# Source_Boat-Board.net
KiCad netlist of a schematic drawn in EasyEDA Pro
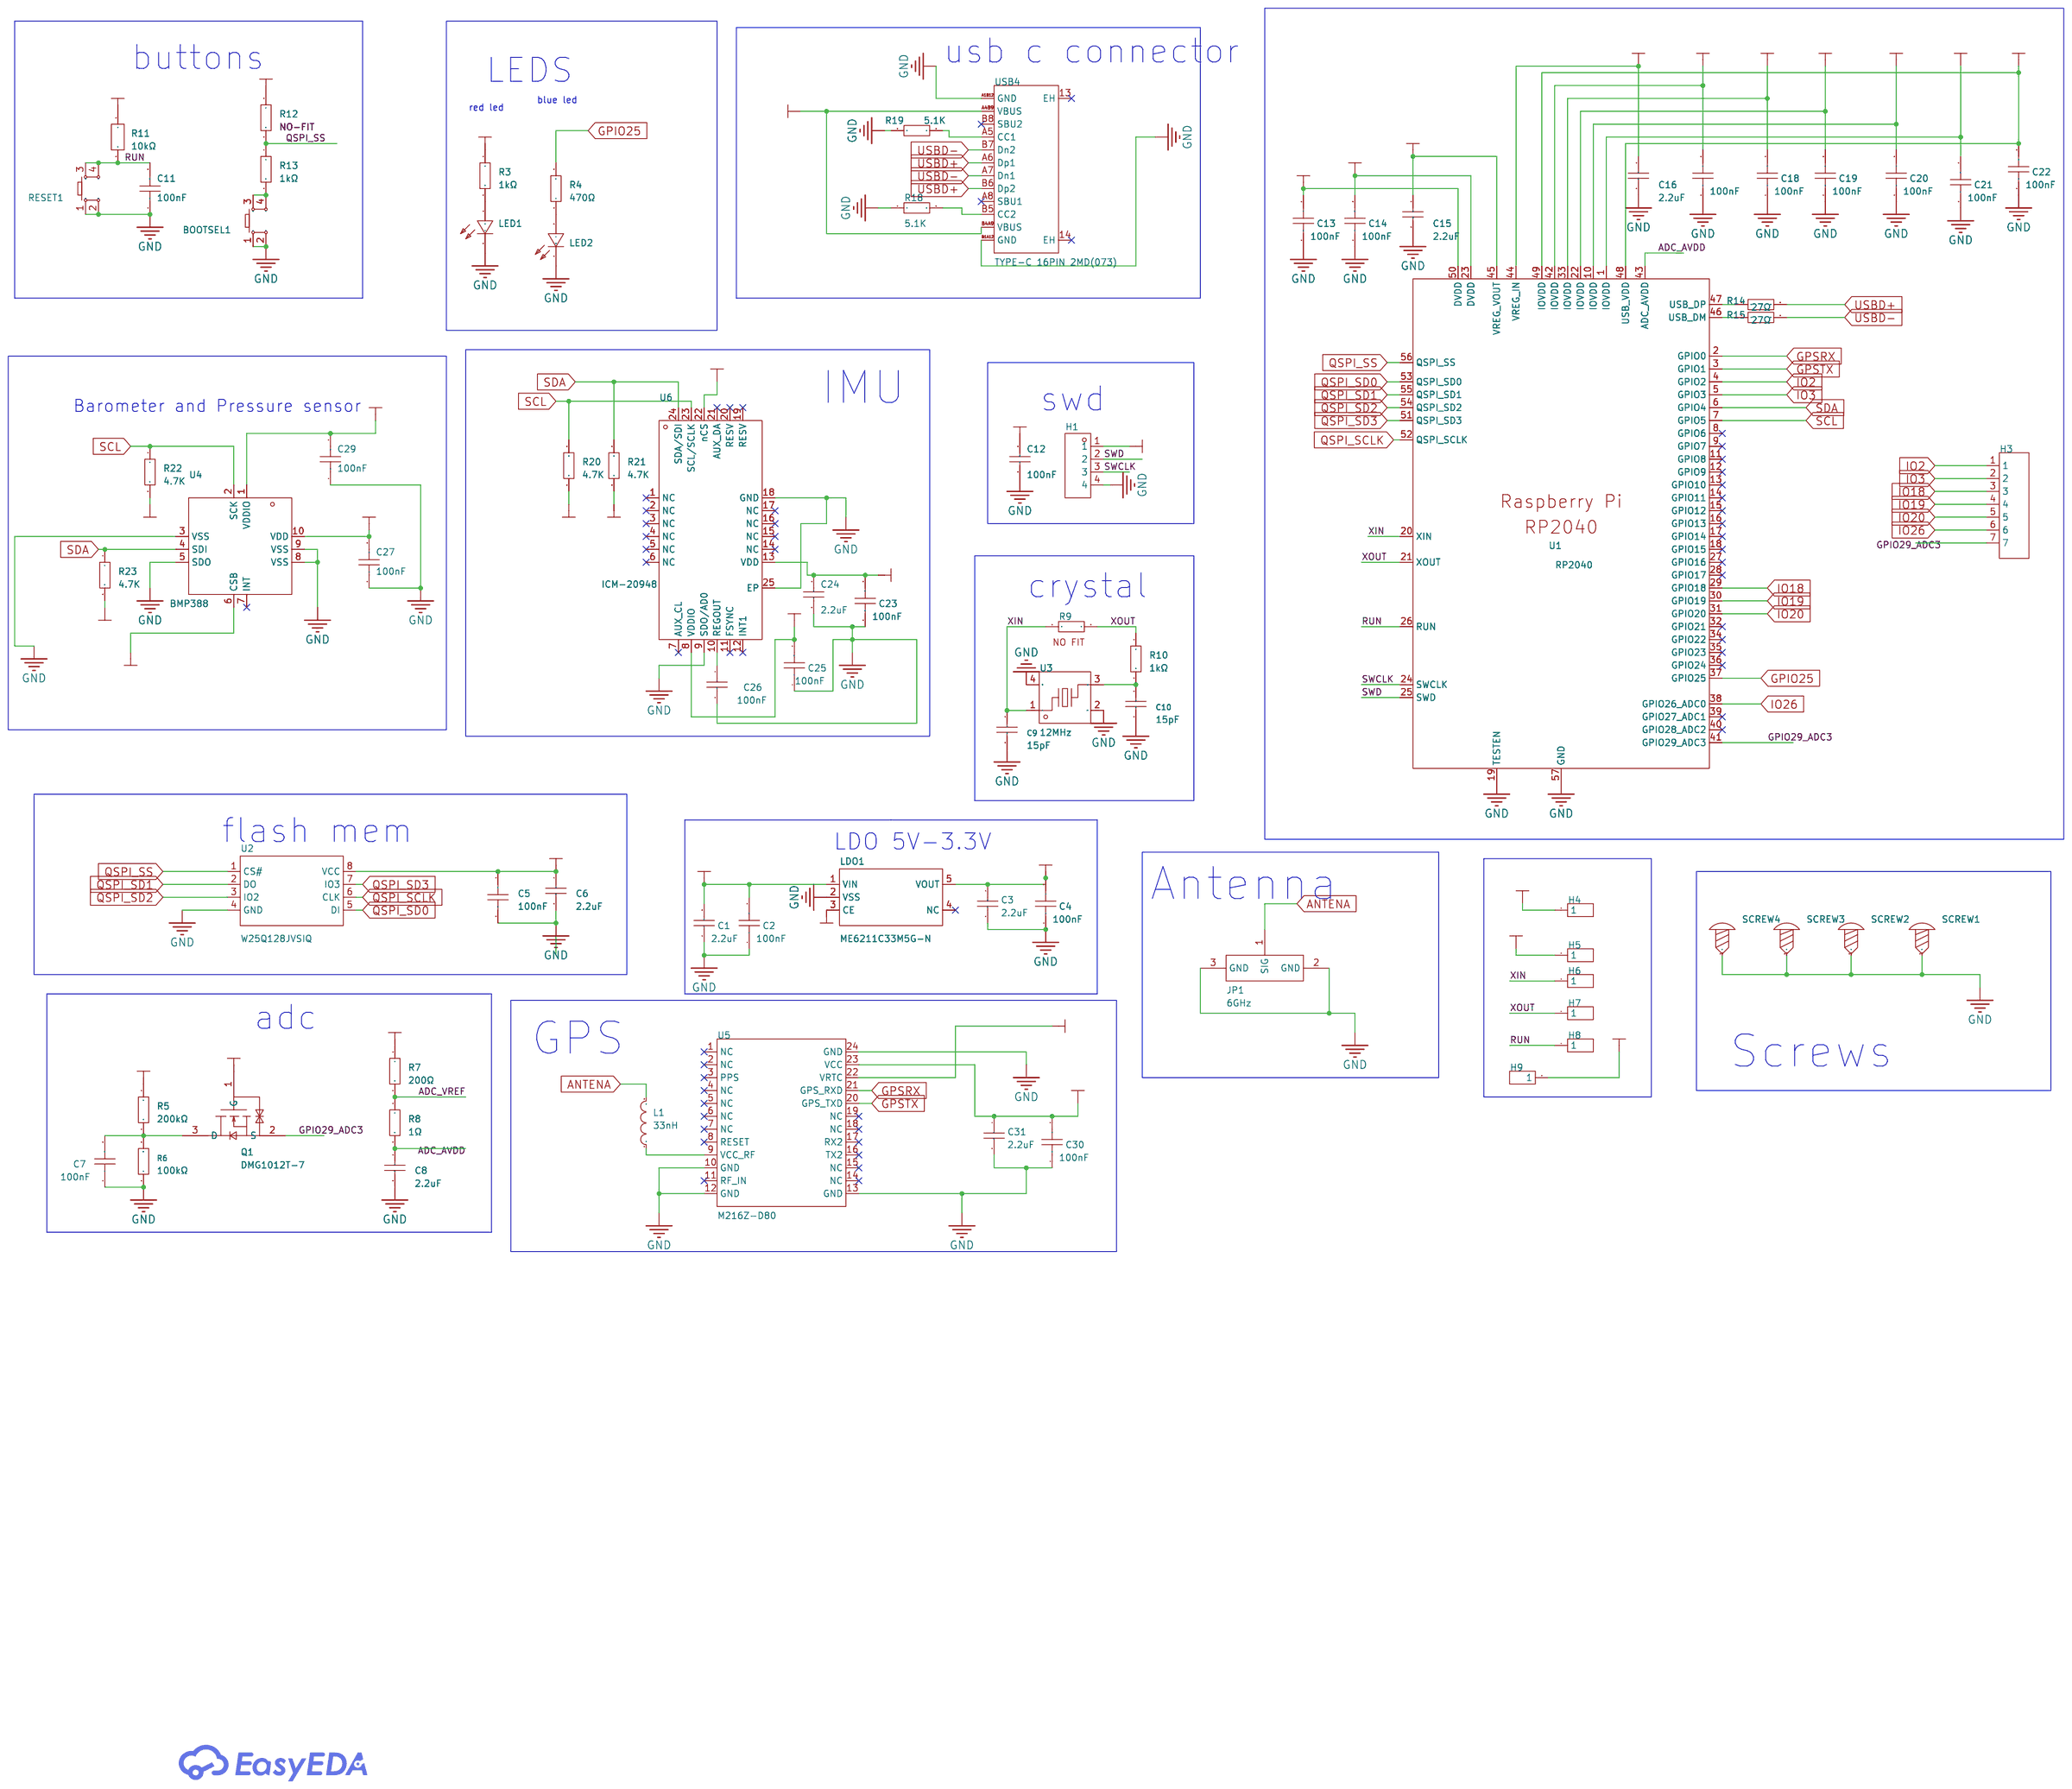
[diagram p0: schematic sheet]

(export (version "E")
  (design (tool "Eeschema 10.0.6"))
  (components
    (comp (ref "BOOTSEL1")
      (value "PTS815SJK250SMTRLFS")
      (footprint "easyedapro:SW-SMD_4P-L4.2-W3.3-P2.15-LS5.1")
      (description "操作寿命10万次，使用温度-20°C 至 70°C,尺寸4.20mmx3.20mmx2.50mm，操作力度2.5N")
      (fields (field (name "Manufacturer") "C&K"))
      (libsource (lib "easyedapro") (part "PTS815SJK250SMTRLFS"))
    )
    (comp (ref "C1")
      (value "2.2uF")
      (footprint "easyedapro:C0603")
      (description "Capacitance:2.2uF Tolerance:±10% Tolerance:±10% Voltage Rating:16V Temperature Coefficient:X5R")
      (fields
        (field (name "Manufacturer Part") "CL10A225KO8NNNC")
        (field (name "Manufacturer") "SAMSUNG(三星)")
      )
      (libsource (lib "easyedapro") (part "CL10A225KO8NNNC"))
    )
    (comp (ref "C2")
      (value "100nF")
      (footprint "easyedapro:C0603")
      (description "Capacitance:100nF Tolerance:±10% Tolerance:±10% Voltage Rating:50V Temperature Coefficient:X7R")
      (fields (field (name "Manufacturer Part") "0603B104K500AT") (field (name "Manufacturer") "FH(风华)"))
      (libsource (lib "easyedapro") (part "0603B104K500AT"))
    )
    (comp (ref "C3")
      (value "2.2uF")
      (footprint "easyedapro:C0603")
      (description "Capacitance:2.2uF Tolerance:±10% Tolerance:±10% Voltage Rating:16V Temperature Coefficient:X5R")
      (fields
        (field (name "Manufacturer Part") "CL10A225KO8NNNC")
        (field (name "Manufacturer") "SAMSUNG(三星)")
      )
      (libsource (lib "easyedapro") (part "CL10A225KO8NNNC"))
    )
    (comp (ref "C4")
      (value "100nF")
      (footprint "easyedapro:C0603")
      (description "Capacitance:100nF Tolerance:±10% Tolerance:±10% Voltage Rating:50V Temperature Coefficient:X7R")
      (fields (field (name "Manufacturer Part") "0603B104K500AT") (field (name "Manufacturer") "FH(风华)"))
      (libsource (lib "easyedapro") (part "0603B104K500AT"))
    )
    (comp (ref "C5")
      (value "100nF")
      (footprint "easyedapro:C0603")
      (description "Capacitance:100nF Tolerance:±10% Tolerance:±10% Voltage Rating:50V Temperature Coefficient:X7R")
      (fields
        (field (name "Manufacturer Part") "CC0603KRX7R9BB104")
        (field (name "Manufacturer") "YAGEO(国巨)")
      )
      (libsource (lib "easyedapro") (part "CC0603KRX7R9BB104"))
    )
    (comp (ref "C6")
      (value "2.2uF")
      (footprint "easyedapro:C0603")
      (description "Capacitance:2.2uF Tolerance:±10% Tolerance:±10% Voltage Rating:16V Temperature Coefficient:X5R")
      (fields
        (field (name "Manufacturer Part") "CL10A225KO8NNNC")
        (field (name "Manufacturer") "SAMSUNG(三星)")
      )
      (libsource (lib "easyedapro") (part "CL10A225KO8NNNC"))
    )
    (comp (ref "C7")
      (value "100nF")
      (footprint "easyedapro:C0603")
      (description "Capacitance:100nF Tolerance:±10% Tolerance:±10% Voltage Rating:50V Temperature Coefficient:X7R")
      (fields
        (field (name "Manufacturer Part") "CC0603KRX7R9BB104")
        (field (name "Manufacturer") "YAGEO(国巨)")
      )
      (libsource (lib "easyedapro") (part "CC0603KRX7R9BB104"))
    )
    (comp (ref "C8")
      (value "2.2uF")
      (footprint "easyedapro:C0603")
      (description "Capacitance:2.2uF Tolerance:±10% Tolerance:±10% Voltage Rating:16V Temperature Coefficient:X5R")
      (fields
        (field (name "Manufacturer Part") "CL10A225KO8NNNC")
        (field (name "Manufacturer") "SAMSUNG(三星)")
      )
      (libsource (lib "easyedapro") (part "CL10A225KO8NNNC"))
    )
    (comp (ref "C9")
      (value "15pF")
      (footprint "easyedapro:C0603")
      (description "Capacitance:15pF Tolerance:±5% Tolerance:±5% Voltage Rating:50V Temperature Coefficient:NP0")
      (fields
        (field (name "Manufacturer Part") "CC0603JRNPO9BN150")
        (field (name "Manufacturer") "YAGEO(国巨)")
      )
      (libsource (lib "easyedapro") (part "CC0603JRNPO9BN150"))
    )
    (comp (ref "C10")
      (value "15pF")
      (footprint "easyedapro:C0603")
      (description "Capacitance:15pF Tolerance:±5% Tolerance:±5% Voltage Rating:50V Temperature Coefficient:NP0")
      (fields
        (field (name "Manufacturer Part") "CC0603JRNPO9BN150")
        (field (name "Manufacturer") "YAGEO(国巨)")
      )
      (libsource (lib "easyedapro") (part "CC0603JRNPO9BN150"))
    )
    (comp (ref "C11")
      (value "100nF")
      (footprint "easyedapro:C0603")
      (description "Capacitance:100nF Tolerance:±10% Tolerance:±10% Voltage Rating:50V Temperature Coefficient:X7R")
      (fields (field (name "Manufacturer Part") "0603B104K500AT") (field (name "Manufacturer") "FH(风华)"))
      (libsource (lib "easyedapro") (part "0603B104K500AT"))
    )
    (comp (ref "C12")
      (value "100nF")
      (footprint "easyedapro:C0603")
      (description "Capacitance:100nF Tolerance:±10% Tolerance:±10% Voltage Rating:50V Temperature Coefficient:X7R")
      (fields (field (name "Manufacturer Part") "0603B104K500NT") (field (name "Manufacturer") "FH(风华)"))
      (libsource (lib "easyedapro") (part "0603B104K500NT"))
    )
    (comp (ref "C13")
      (value "100nF")
      (footprint "easyedapro:C0603")
      (description "Capacitance:100nF Tolerance:±10% Tolerance:±10% Voltage Rating:50V Temperature Coefficient:X7R")
      (fields (field (name "Manufacturer Part") "0603B104K500AT") (field (name "Manufacturer") "FH(风华)"))
      (libsource (lib "easyedapro") (part "0603B104K500AT"))
    )
    (comp (ref "C14")
      (value "100nF")
      (footprint "easyedapro:C0603")
      (description "Capacitance:100nF Tolerance:±10% Tolerance:±10% Voltage Rating:50V Temperature Coefficient:X7R")
      (fields (field (name "Manufacturer Part") "0603B104K500AT") (field (name "Manufacturer") "FH(风华)"))
      (libsource (lib "easyedapro") (part "0603B104K500AT"))
    )
    (comp (ref "C15")
      (value "2.2uF")
      (footprint "easyedapro:C0603")
      (description "Capacitance:2.2uF Tolerance:±10% Tolerance:±10% Voltage Rating:16V Temperature Coefficient:X5R")
      (fields
        (field (name "Manufacturer Part") "CL10A225KO8NNNC")
        (field (name "Manufacturer") "SAMSUNG(三星)")
      )
      (libsource (lib "easyedapro") (part "CL10A225KO8NNNC"))
    )
    (comp (ref "C16")
      (value "2.2uF")
      (footprint "easyedapro:C0603")
      (description "Capacitance:2.2uF Tolerance:±10% Tolerance:±10% Voltage Rating:16V Temperature Coefficient:X5R")
      (fields
        (field (name "Manufacturer Part") "CL10A225KO8NNNC")
        (field (name "Manufacturer") "SAMSUNG(三星)")
      )
      (libsource (lib "easyedapro") (part "CL10A225KO8NNNC"))
    )
    (comp (ref "C17")
      (value "100nF")
      (footprint "easyedapro:C0603")
      (description "Capacitance:100nF Tolerance:±10% Tolerance:±10% Voltage Rating:50V Temperature Coefficient:X7R")
      (fields (field (name "Manufacturer Part") "0603B104K500AT") (field (name "Manufacturer") "FH(风华)"))
      (libsource (lib "easyedapro") (part "0603B104K500AT"))
    )
    (comp (ref "C18")
      (value "100nF")
      (footprint "easyedapro:C0603")
      (description "Capacitance:100nF Tolerance:±10% Tolerance:±10% Voltage Rating:50V Temperature Coefficient:X7R")
      (fields (field (name "Manufacturer Part") "0603B104K500AT") (field (name "Manufacturer") "FH(风华)"))
      (libsource (lib "easyedapro") (part "0603B104K500AT"))
    )
    (comp (ref "C19")
      (value "100nF")
      (footprint "easyedapro:C0603")
      (description "Capacitance:100nF Tolerance:±10% Tolerance:±10% Voltage Rating:50V Temperature Coefficient:X7R")
      (fields (field (name "Manufacturer Part") "0603B104K500AT") (field (name "Manufacturer") "FH(风华)"))
      (libsource (lib "easyedapro") (part "0603B104K500AT"))
    )
    (comp (ref "C20")
      (value "100nF")
      (footprint "easyedapro:C0603")
      (description "Capacitance:100nF Tolerance:±10% Tolerance:±10% Voltage Rating:50V Temperature Coefficient:X7R")
      (fields (field (name "Manufacturer Part") "0603B104K500AT") (field (name "Manufacturer") "FH(风华)"))
      (libsource (lib "easyedapro") (part "0603B104K500AT"))
    )
    (comp (ref "C21")
      (value "100nF")
      (footprint "easyedapro:C0603")
      (description "Capacitance:100nF Tolerance:±10% Tolerance:±10% Voltage Rating:50V Temperature Coefficient:X7R")
      (fields (field (name "Manufacturer Part") "0603B104K500AT") (field (name "Manufacturer") "FH(风华)"))
      (libsource (lib "easyedapro") (part "0603B104K500AT"))
    )
    (comp (ref "C22")
      (value "100nF")
      (footprint "easyedapro:C0603")
      (description "Capacitance:100nF Tolerance:±10% Tolerance:±10% Voltage Rating:50V Temperature Coefficient:X7R")
      (fields (field (name "Manufacturer Part") "0603B104K500AT") (field (name "Manufacturer") "FH(风华)"))
      (libsource (lib "easyedapro") (part "0603B104K500AT"))
    )
    (comp (ref "C23")
      (value "100nF")
      (footprint "easyedapro:C0603")
      (description "Capacitance:100nF Tolerance:±10% Tolerance:±10% Voltage Rating:50V Temperature Coefficient:X7R")
      (fields (field (name "Manufacturer Part") "0603B104K500AT") (field (name "Manufacturer") "FH(风华)"))
      (libsource (lib "easyedapro") (part "0603B104K500AT"))
    )
    (comp (ref "C24")
      (value "2.2uF")
      (footprint "easyedapro:C0603")
      (description "Capacitance:2.2uF Tolerance:±10% Tolerance:±10% Voltage Rating:16V Temperature Coefficient:X5R")
      (fields
        (field (name "Manufacturer Part") "CL10A225KO8NNNC")
        (field (name "Manufacturer") "SAMSUNG(三星)")
      )
      (libsource (lib "easyedapro") (part "CL10A225KO8NNNC"))
    )
    (comp (ref "C25")
      (value "100nF")
      (footprint "easyedapro:C0603")
      (description "Capacitance:100nF Tolerance:±10% Tolerance:±10% Voltage Rating:50V Temperature Coefficient:X7R")
      (fields (field (name "Manufacturer Part") "0603B104K500AT") (field (name "Manufacturer") "FH(风华)"))
      (libsource (lib "easyedapro") (part "0603B104K500AT"))
    )
    (comp (ref "C26")
      (value "100nF")
      (footprint "easyedapro:C0603")
      (description "Capacitance:100nF Tolerance:±10% Tolerance:±10% Voltage Rating:50V Temperature Coefficient:X7R")
      (fields (field (name "Manufacturer Part") "0603B104K500NT") (field (name "Manufacturer") "FH(风华)"))
      (libsource (lib "easyedapro") (part "0603B104K500NT"))
    )
    (comp (ref "C27")
      (value "100nF")
      (footprint "easyedapro:C0603")
      (description "Capacitance:100nF Tolerance:±10% Tolerance:±10% Voltage Rating:50V Temperature Coefficient:X7R")
      (fields (field (name "Manufacturer Part") "0603B104K500AT") (field (name "Manufacturer") "FH(风华)"))
      (libsource (lib "easyedapro") (part "0603B104K500AT"))
    )
    (comp (ref "C29")
      (value "100nF")
      (footprint "easyedapro:C0603")
      (description "Capacitance:100nF Tolerance:±10% Tolerance:±10% Voltage Rating:50V Temperature Coefficient:X7R")
      (fields (field (name "Manufacturer Part") "0603B104K500AT") (field (name "Manufacturer") "FH(风华)"))
      (libsource (lib "easyedapro") (part "0603B104K500AT"))
    )
    (comp (ref "C30")
      (value "100nF")
      (footprint "easyedapro:C0603")
      (description "Capacitance:100nF Tolerance:±10% Tolerance:±10% Voltage Rating:50V Temperature Coefficient:X7R")
      (fields (field (name "Manufacturer Part") "0603B104K500AT") (field (name "Manufacturer") "FH(风华)"))
      (libsource (lib "easyedapro") (part "0603B104K500AT"))
    )
    (comp (ref "C31")
      (value "2.2uF")
      (footprint "easyedapro:C0603")
      (description "Capacitance:2.2uF Tolerance:±10% Tolerance:±10% Voltage Rating:16V Temperature Coefficient:X5R")
      (fields
        (field (name "Manufacturer Part") "CL10A225KO8NNNC")
        (field (name "Manufacturer") "SAMSUNG(三星)")
      )
      (libsource (lib "easyedapro") (part "CL10A225KO8NNNC"))
    )
    (comp (ref "H1")
      (value "DZ254W-11-04-65")
      (footprint "easyedapro:HDR-TH_4P-P2.54-H-M-W10.3")
      (fields (field (name "Manufacturer") "DEALON(德艺隆)"))
      (libsource (lib "easyedapro") (part "DZ254W-11-04-65"))
    )
    (comp (ref "H3")
      (value "~")
      (footprint "easyedapro:HDR-TH_7P-P2.54-V-F")
      (libsource (lib "easyedapro") (part "220S-1*7P H=8.5MM Ytype Gold-plated"))
    )
    (comp (ref "H4")
      (value "~")
      (footprint "easyedapro:HDR-TH_1P-V-M_XKB_X4611WV-01I-C28D40")
      (libsource (lib "easyedapro") (part "HDR_1x1"))
    )
    (comp (ref "H5")
      (value "~")
      (footprint "easyedapro:HDR-TH_1P-V-M_XKB_X4611WV-01I-C28D40")
      (libsource (lib "easyedapro") (part "HDR_1x1"))
    )
    (comp (ref "H6")
      (value "~")
      (footprint "easyedapro:HDR-TH_1P-V-M_XKB_X4611WV-01I-C28D40")
      (libsource (lib "easyedapro") (part "HDR_1x1"))
    )
    (comp (ref "H7")
      (value "~")
      (footprint "easyedapro:HDR-TH_1P-V-M_XKB_X4611WV-01I-C28D40")
      (libsource (lib "easyedapro") (part "HDR_1x1"))
    )
    (comp (ref "H8")
      (value "~")
      (footprint "easyedapro:HDR-TH_1P-V-M_XKB_X4611WV-01I-C28D40")
      (libsource (lib "easyedapro") (part "HDR_1x1"))
    )
    (comp (ref "H9")
      (value "~")
      (footprint "easyedapro:HDR-TH_1P-V-M_XKB_X4611WV-01I-C28D40")
      (libsource (lib "easyedapro") (part "HDR_1x1"))
    )
    (comp (ref "JP1")
      (value "6GHz")
      (footprint "easyedapro:RF-SMD_FRF05002-JSS103M")
      (fields (field (name "Manufacturer Part") "U.FL-R-SMT-1(80)") (field (name "Manufacturer") "HRS(广濑)"))
      (libsource (lib "easyedapro") (part "U.FL-R-SMT-1(80)"))
    )
    (comp (ref "L1") (value "33nH") (footprint "easyedapro:L0603") (libsource (lib "easyedapro") (part "电感")))
    (comp (ref "LDO1")
      (value "ME6211C33M5G-N")
      (footprint "easyedapro:SOT-23-5_L3.0-W1.7-P0.95-LS2.8-BL")
      (fields (field (name "Manufacturer") "MICRONE(南京微盟)"))
      (libsource (lib "easyedapro") (part "ME6211C33M5G-N"))
    )
    (comp (ref "LED1")
      (value "NCD0603R1")
      (footprint "easyedapro:LED0603-RD_RED")
      (fields (field (name "Manufacturer") "国星光电"))
      (libsource (lib "easyedapro") (part "FC-DA1608HRK-620D"))
    )
    (comp (ref "LED2")
      (value "19-217/BHC-ZL1M2RY/3T")
      (footprint "easyedapro:LED0603-FD_BLUE")
      (fields (field (name "Manufacturer") "EVERLIGHT(亿光)"))
      (libsource (lib "easyedapro") (part "19-217/BHC-ZL1M2RY/3T"))
    )
    (comp (ref "Q1")
      (value "DMG1012T-7")
      (footprint "easyedapro:SOT-523-3_L1.6-W0.8-P1.00-LS1.6-BR")
      (fields (field (name "Manufacturer") "DIODES(美台)"))
      (libsource (lib "easyedapro") (part "DMG1012T-7"))
    )
    (comp (ref "R3")
      (value "1kΩ")
      (footprint "easyedapro:R0603")
      (fields (field (name "Manufacturer Part") "RC0603FR-071KL") (field (name "Manufacturer") "YAGEO(国巨)"))
      (libsource (lib "easyedapro") (part "RC0603FR-071KL"))
    )
    (comp (ref "R4")
      (value "470Ω")
      (footprint "easyedapro:R0603")
      (fields (field (name "Manufacturer Part") "RC0603FR-07470RL") (field (name "Manufacturer") "YAGEO(国巨)"))
      (libsource (lib "easyedapro") (part "RC0603FR-07470RL"))
    )
    (comp (ref "R5")
      (value "200kΩ")
      (footprint "easyedapro:R0603")
      (fields (field (name "Manufacturer Part") "RC0603FR-07200KL") (field (name "Manufacturer") "YAGEO(国巨)"))
      (libsource (lib "easyedapro") (part "RC0603FR-07200KL"))
    )
    (comp (ref "R6")
      (value "100kΩ")
      (footprint "easyedapro:R0603")
      (fields (field (name "Manufacturer Part") "RC0603FR-07100KL") (field (name "Manufacturer") "YAGEO(国巨)"))
      (libsource (lib "easyedapro") (part "RC0603FR-07100KL"))
    )
    (comp (ref "R7")
      (value "200Ω")
      (footprint "easyedapro:R0603")
      (fields (field (name "Manufacturer Part") "RC0603FR-07200RL") (field (name "Manufacturer") "YAGEO(国巨)"))
      (libsource (lib "easyedapro") (part "RC0603FR-07200RL"))
    )
    (comp (ref "R8")
      (value "1Ω")
      (footprint "easyedapro:R0603")
      (fields (field (name "Manufacturer Part") "RC0603FR-071RL") (field (name "Manufacturer") "YAGEO(国巨)"))
      (libsource (lib "easyedapro") (part "RC0603FR-071RL"))
    )
    (comp (ref "R9")
      (value "NO FIT")
      (footprint "easyedapro:R0603")
      (libsource (lib "easyedapro") (part "Res"))
    )
    (comp (ref "R10")
      (value "1kΩ")
      (footprint "easyedapro:R0603")
      (fields (field (name "Manufacturer Part") "RC0603FR-071KL") (field (name "Manufacturer") "YAGEO(国巨)"))
      (libsource (lib "easyedapro") (part "RC0603FR-071KL"))
    )
    (comp (ref "R11")
      (value "10kΩ")
      (footprint "easyedapro:R0603")
      (fields
        (field (name "Manufacturer Part") "NQ03WAF1002T5E")
        (field (name "Manufacturer") "UNI-ROYAL(厚声)")
      )
      (libsource (lib "easyedapro") (part "NQ03WAF1002T5E"))
    )
    (comp (ref "R12")
      (value "NO-FIT")
      (footprint "easyedapro:R0603")
      (libsource (lib "easyedapro") (part "Res"))
    )
    (comp (ref "R13")
      (value "1kΩ")
      (footprint "easyedapro:R0603")
      (fields (field (name "Manufacturer Part") "RC0603FR-071KL") (field (name "Manufacturer") "YAGEO(国巨)"))
      (libsource (lib "easyedapro") (part "RC0603FR-071KL"))
    )
    (comp (ref "R14")
      (value "27Ω")
      (footprint "easyedapro:R0603")
      (description "电阻类型:厚膜电阻;阻值:27Ω;精度:±1%;功率:100mW;温度系数:±200ppm/°C;最大工作电压:75V;工作温度范围:-55°C~+155°C;")
      (fields
        (field (name "Manufacturer Part") "0603WAF270JT5E")
        (field (name "Manufacturer") "UNI-ROYAL(厚声)")
      )
      (libsource (lib "easyedapro") (part "0603WAF270JT5E"))
    )
    (comp (ref "R15")
      (value "27Ω")
      (footprint "easyedapro:R0603")
      (description "电阻类型:厚膜电阻;阻值:27Ω;精度:±1%;功率:100mW;温度系数:±200ppm/°C;最大工作电压:75V;工作温度范围:-55°C~+155°C;")
      (fields
        (field (name "Manufacturer Part") "0603WAF270JT5E")
        (field (name "Manufacturer") "UNI-ROYAL(厚声)")
      )
      (libsource (lib "easyedapro") (part "0603WAF270JT5E"))
    )
    (comp (ref "R18")
      (value "5.1K")
      (footprint "easyedapro:R0603")
      (libsource (lib "easyedapro") (part "Res"))
    )
    (comp (ref "R19")
      (value "5.1K")
      (footprint "easyedapro:R0603")
      (libsource (lib "easyedapro") (part "Res"))
    )
    (comp (ref "R20")
      (value "4.7K")
      (footprint "easyedapro:R0603")
      (libsource (lib "easyedapro") (part "Res"))
    )
    (comp (ref "R21")
      (value "4.7K")
      (footprint "easyedapro:R0603")
      (libsource (lib "easyedapro") (part "Res"))
    )
    (comp (ref "R22")
      (value "4.7K")
      (footprint "easyedapro:R0603")
      (libsource (lib "easyedapro") (part "Res"))
    )
    (comp (ref "R23")
      (value "4.7K")
      (footprint "easyedapro:R0603")
      (libsource (lib "easyedapro") (part "Res"))
    )
    (comp (ref "RESET1")
      (value "PTS815SJK250SMTRLFS")
      (footprint "easyedapro:SW-SMD_4P-L4.2-W3.3-P2.15-LS5.1")
      (description "操作寿命10万次，使用温度-20°C 至 70°C,尺寸4.20mmx3.20mmx2.50mm，操作力度2.5N")
      (fields (field (name "Manufacturer") "C&K"))
      (libsource (lib "easyedapro") (part "PTS815SJK250SMTRLFS"))
    )
    (comp (ref "SCREW1")
      (value "~")
      (footprint "easyedapro:Screw-Hole-M2")
      (libsource (lib "easyedapro") (part "Screw-Hole"))
    )
    (comp (ref "SCREW2")
      (value "~")
      (footprint "easyedapro:Screw-Hole-M2")
      (libsource (lib "easyedapro") (part "Screw-Hole"))
    )
    (comp (ref "SCREW3")
      (value "~")
      (footprint "easyedapro:Screw-Hole-M2")
      (libsource (lib "easyedapro") (part "Screw-Hole"))
    )
    (comp (ref "SCREW4")
      (value "~")
      (footprint "easyedapro:Screw-Hole-M2")
      (libsource (lib "easyedapro") (part "Screw-Hole"))
    )
    (comp (ref "U1")
      (value "RP2040")
      (footprint "easyedapro:LQFN-56_L7.0-W7.0-P0.4-EP")
      (description "CPU Core:- CPU Maximum Speed:133MHz Number of I/O:30 ADC (Bit):12bit")
      (fields (field (name "Manufacturer") "Raspberry Pi(树莓派)"))
      (libsource (lib "easyedapro") (part "RP2040"))
    )
    (comp (ref "U2")
      (value "W25Q128JVSIQ")
      (footprint "easyedapro:SOIC-8_L5.3-W5.3-P1.27-LS8.0-BL")
      (fields (field (name "Manufacturer") "Winbond(华邦)"))
      (libsource (lib "easyedapro") (part "W25Q128JVSIQTR"))
    )
    (comp (ref "U3")
      (value "12MHz")
      (footprint "easyedapro:CRYSTAL-SMD_4P-L3.2-W2.5-BL")
      (fields
        (field (name "Manufacturer Part") "0132M412000F10FTNNL")
        (field (name "Manufacturer") "HCI(杭晶)")
      )
      (libsource (lib "easyedapro") (part "0132M412000F10FTNNL"))
    )
    (comp (ref "U4")
      (value "BMP388")
      (footprint "easyedapro:SENSORM-SMD_BMP388")
      (fields (field (name "Manufacturer") "Bosch(博世)"))
      (libsource (lib "easyedapro") (part "BMP388"))
    )
    (comp (ref "U5")
      (value "M216Z-D80")
      (footprint "easyedapro:LCC-24_L16.3-W12.2_NEO-NEO-M10")
      (fields (field (name "Manufacturer") "如般微"))
      (libsource (lib "easyedapro") (part "M216Z-D80"))
    )
    (comp (ref "U6")
      (value "ICM-20948")
      (footprint "easyedapro:QFN-24_L3.0-W3.0-P0.40-BL-EP")
      (fields (field (name "Manufacturer") "TDK InvenSense(应美盛)"))
      (libsource (lib "easyedapro") (part "ICM-20948"))
    )
    (comp (ref "USB4")
      (value "TYPE-C 16PIN 2MD(073)")
      (footprint "easyedapro:USB-C-SMD_TYPE-C-16PIN-2MD-073")
      (fields (field (name "Manufacturer") "SHOU HAN(首韩)"))
      (libsource (lib "easyedapro") (part "TYPE-C 16PIN 2MD(073)"))
    )
  )
  (nets
    (net (code "1") (name "/ADC_AVDD") (class "Default")
      (node (ref "C8") (pin "1") (pinfunction "1_1") (pintype "input"))
      (node (ref "R8") (pin "2") (pinfunction "2_2") (pintype "input"))
      (node (ref "U1") (pin "43") (pinfunction "ADC_AVDD_43") (pintype "bidirectional"))
    )
    (net (code "2") (name "/ADC_VREF") (class "Default")
      (node (ref "R7") (pin "2") (pinfunction "2_2") (pintype "input"))
      (node (ref "R8") (pin "1") (pinfunction "1_1") (pintype "input"))
    )
    (net (code "3") (name "/GPIO29_ADC3") (class "Default")
      (node (ref "H3") (pin "7") (pinfunction "7_7") (pintype "unspecified"))
      (node (ref "Q1") (pin "2") (pinfunction "S_2") (pintype "unspecified"))
      (node (ref "U1") (pin "41") (pinfunction "GPIO29_ADC3_41") (pintype "bidirectional"))
    )
    (net (code "4") (name "/RUN") (class "Default")
      (node (ref "C11") (pin "2") (pinfunction "2_2") (pintype "unspecified"))
      (node (ref "H8") (pin "1") (pinfunction "1_1") (pintype "unspecified"))
      (node (ref "R11") (pin "2") (pinfunction "2_2") (pintype "unspecified"))
      (node (ref "RESET1") (pin "3") (pinfunction "3_3") (pintype "input"))
      (node (ref "RESET1") (pin "4") (pinfunction "4_4") (pintype "input"))
      (node (ref "U1") (pin "26") (pinfunction "RUN_26") (pintype "input"))
    )
    (net (code "5") (name "/SWCLK") (class "Default")
      (node (ref "H1") (pin "3") (pinfunction "3_3") (pintype "input"))
      (node (ref "U1") (pin "24") (pinfunction "SWCLK_24") (pintype "output"))
    )
    (net (code "6") (name "/SWD") (class "Default")
      (node (ref "H1") (pin "2") (pinfunction "2_2") (pintype "input"))
      (node (ref "U1") (pin "25") (pinfunction "SWD_25") (pintype "bidirectional"))
    )
    (net (code "7") (name "/XIN") (class "Default")
      (node (ref "C9") (pin "2") (pinfunction "2_2") (pintype "input"))
      (node (ref "H6") (pin "1") (pinfunction "1_1") (pintype "unspecified"))
      (node (ref "R9") (pin "1") (pinfunction "1_1") (pintype "input"))
      (node (ref "U1") (pin "20") (pinfunction "XIN_20") (pintype "input"))
      (node (ref "U3") (pin "1") (pinfunction "1_1") (pintype "input"))
    )
    (net (code "8") (name "/XOUT") (class "Default")
      (node (ref "H7") (pin "1") (pinfunction "1_1") (pintype "unspecified"))
      (node (ref "R10") (pin "1") (pinfunction "1_1") (pintype "input"))
      (node (ref "R9") (pin "2") (pinfunction "2_2") (pintype "input"))
      (node (ref "U1") (pin "21") (pinfunction "XOUT_21") (pintype "unspecified"))
    )
    (net (code "9") (name "1V1") (class "Default")
      (node (ref "C13") (pin "2") (pinfunction "2_2") (pintype "unspecified"))
      (node (ref "C14") (pin "2") (pinfunction "2_2") (pintype "unspecified"))
      (node (ref "C15") (pin "1") (pinfunction "1_1") (pintype "input"))
      (node (ref "H5") (pin "1") (pinfunction "1_1") (pintype "unspecified"))
      (node (ref "U1") (pin "23") (pinfunction "DVDD_23") (pintype "bidirectional"))
      (node (ref "U1") (pin "45") (pinfunction "VREG_VOUT_45") (pintype "bidirectional"))
      (node (ref "U1") (pin "50") (pinfunction "DVDD_50") (pintype "bidirectional"))
    )
    (net (code "10") (name "3V3") (class "Default")
      (node (ref "C12") (pin "1") (pinfunction "1_1") (pintype "input"))
      (node (ref "C16") (pin "1") (pinfunction "1_1") (pintype "input"))
      (node (ref "C17") (pin "2") (pinfunction "2_2") (pintype "unspecified"))
      (node (ref "C18") (pin "2") (pinfunction "2_2") (pintype "unspecified"))
      (node (ref "C19") (pin "2") (pinfunction "2_2") (pintype "unspecified"))
      (node (ref "C20") (pin "2") (pinfunction "2_2") (pintype "unspecified"))
      (node (ref "C21") (pin "2") (pinfunction "2_2") (pintype "unspecified"))
      (node (ref "C22") (pin "2") (pinfunction "2_2") (pintype "unspecified"))
      (node (ref "C23") (pin "2") (pinfunction "2_2") (pintype "unspecified"))
      (node (ref "C24") (pin "1") (pinfunction "1_1") (pintype "input"))
      (node (ref "C25") (pin "2") (pinfunction "2_2") (pintype "unspecified"))
      (node (ref "C27") (pin "2") (pinfunction "2_2") (pintype "unspecified"))
      (node (ref "C29") (pin "2") (pinfunction "2_2") (pintype "unspecified"))
      (node (ref "C3") (pin "1") (pinfunction "1_1") (pintype "input"))
      (node (ref "C30") (pin "2") (pinfunction "2_2") (pintype "unspecified"))
      (node (ref "C31") (pin "1") (pinfunction "1_1") (pintype "input"))
      (node (ref "C4") (pin "2") (pinfunction "2_2") (pintype "unspecified"))
      (node (ref "C5") (pin "1") (pinfunction "1_1") (pintype "unspecified"))
      (node (ref "C6") (pin "1") (pinfunction "1_1") (pintype "input"))
      (node (ref "H1") (pin "1") (pinfunction "1_1") (pintype "input"))
      (node (ref "H4") (pin "1") (pinfunction "1_1") (pintype "unspecified"))
      (node (ref "LDO1") (pin "5") (pinfunction "VOUT_5") (pintype "unspecified"))
      (node (ref "Q1") (pin "1") (pinfunction "G_1") (pintype "unspecified"))
      (node (ref "R11") (pin "1") (pinfunction "1_1") (pintype "unspecified"))
      (node (ref "R12") (pin "1") (pinfunction "1_1") (pintype "input"))
      (node (ref "R20") (pin "2") (pinfunction "2_2") (pintype "input"))
      (node (ref "R21") (pin "2") (pinfunction "2_2") (pintype "input"))
      (node (ref "R22") (pin "2") (pinfunction "2_2") (pintype "input"))
      (node (ref "R23") (pin "2") (pinfunction "2_2") (pintype "input"))
      (node (ref "R3") (pin "1") (pinfunction "1_1") (pintype "input"))
      (node (ref "R7") (pin "1") (pinfunction "1_1") (pintype "input"))
      (node (ref "U1") (pin "1") (pinfunction "IOVDD_1") (pintype "bidirectional"))
      (node (ref "U1") (pin "10") (pinfunction "IOVDD_10") (pintype "bidirectional"))
      (node (ref "U1") (pin "22") (pinfunction "IOVDD_22") (pintype "bidirectional"))
      (node (ref "U1") (pin "33") (pinfunction "IOVDD_33") (pintype "bidirectional"))
      (node (ref "U1") (pin "42") (pinfunction "IOVDD_42") (pintype "bidirectional"))
      (node (ref "U1") (pin "44") (pinfunction "VREG_IN_44") (pintype "bidirectional"))
      (node (ref "U1") (pin "48") (pinfunction "USB_VDD_48") (pintype "bidirectional"))
      (node (ref "U1") (pin "49") (pinfunction "IOVDD_49") (pintype "bidirectional"))
      (node (ref "U2") (pin "8") (pinfunction "VCC_8") (pintype "unspecified"))
      (node (ref "U4") (pin "1") (pinfunction "VDDIO_1") (pintype "unspecified"))
      (node (ref "U4") (pin "10") (pinfunction "VDD_10") (pintype "unspecified"))
      (node (ref "U4") (pin "6") (pinfunction "CSB_6") (pintype "unspecified"))
      (node (ref "U5") (pin "22") (pinfunction "VRTC_22") (pintype "unspecified"))
      (node (ref "U5") (pin "23") (pinfunction "VCC_23") (pintype "unspecified"))
      (node (ref "U6") (pin "13") (pinfunction "VDD_13") (pintype "unspecified"))
      (node (ref "U6") (pin "22") (pinfunction "nCS_22") (pintype "unspecified"))
      (node (ref "U6") (pin "8") (pinfunction "VDDIO_8") (pintype "unspecified"))
    )
    (net (code "11") (name "ANTENA") (class "Default")
      (node (ref "JP1") (pin "1") (pinfunction "SIG_1") (pintype "unspecified"))
      (node (ref "L1") (pin "2") (pinfunction "2_2") (pintype "input"))
    )
    (net (code "12") (name "GND") (class "Default")
      (node (ref "BOOTSEL1") (pin "1") (pinfunction "1_1") (pintype "input"))
      (node (ref "BOOTSEL1") (pin "2") (pinfunction "2_2") (pintype "input"))
      (node (ref "C1") (pin "1") (pinfunction "1_1") (pintype "input"))
      (node (ref "C10") (pin "1") (pinfunction "1_1") (pintype "input"))
      (node (ref "C11") (pin "1") (pinfunction "1_1") (pintype "unspecified"))
      (node (ref "C12") (pin "2") (pinfunction "2_2") (pintype "input"))
      (node (ref "C13") (pin "1") (pinfunction "1_1") (pintype "unspecified"))
      (node (ref "C14") (pin "1") (pinfunction "1_1") (pintype "unspecified"))
      (node (ref "C15") (pin "2") (pinfunction "2_2") (pintype "input"))
      (node (ref "C16") (pin "2") (pinfunction "2_2") (pintype "input"))
      (node (ref "C17") (pin "1") (pinfunction "1_1") (pintype "unspecified"))
      (node (ref "C18") (pin "1") (pinfunction "1_1") (pintype "unspecified"))
      (node (ref "C19") (pin "1") (pinfunction "1_1") (pintype "unspecified"))
      (node (ref "C2") (pin "1") (pinfunction "1_1") (pintype "unspecified"))
      (node (ref "C20") (pin "1") (pinfunction "1_1") (pintype "unspecified"))
      (node (ref "C21") (pin "1") (pinfunction "1_1") (pintype "unspecified"))
      (node (ref "C22") (pin "1") (pinfunction "1_1") (pintype "unspecified"))
      (node (ref "C23") (pin "1") (pinfunction "1_1") (pintype "unspecified"))
      (node (ref "C24") (pin "2") (pinfunction "2_2") (pintype "input"))
      (node (ref "C25") (pin "1") (pinfunction "1_1") (pintype "unspecified"))
      (node (ref "C26") (pin "2") (pinfunction "2_2") (pintype "input"))
      (node (ref "C27") (pin "1") (pinfunction "1_1") (pintype "unspecified"))
      (node (ref "C29") (pin "1") (pinfunction "1_1") (pintype "unspecified"))
      (node (ref "C3") (pin "2") (pinfunction "2_2") (pintype "input"))
      (node (ref "C30") (pin "1") (pinfunction "1_1") (pintype "unspecified"))
      (node (ref "C31") (pin "2") (pinfunction "2_2") (pintype "input"))
      (node (ref "C4") (pin "1") (pinfunction "1_1") (pintype "unspecified"))
      (node (ref "C5") (pin "2") (pinfunction "2_2") (pintype "unspecified"))
      (node (ref "C6") (pin "2") (pinfunction "2_2") (pintype "input"))
      (node (ref "C7") (pin "1") (pinfunction "1_1") (pintype "unspecified"))
      (node (ref "C8") (pin "2") (pinfunction "2_2") (pintype "input"))
      (node (ref "C9") (pin "1") (pinfunction "1_1") (pintype "input"))
      (node (ref "H1") (pin "4") (pinfunction "4_4") (pintype "input"))
      (node (ref "JP1") (pin "2") (pinfunction "GND_2") (pintype "unspecified"))
      (node (ref "JP1") (pin "3") (pinfunction "GND_3") (pintype "unspecified"))
      (node (ref "LDO1") (pin "2") (pinfunction "VSS_2") (pintype "unspecified"))
      (node (ref "LED1") (pin "1") (pinfunction "K_1") (pintype "input"))
      (node (ref "LED2") (pin "1") (pinfunction "C_1") (pintype "input"))
      (node (ref "R18") (pin "1") (pinfunction "1_1") (pintype "input"))
      (node (ref "R19") (pin "1") (pinfunction "1_1") (pintype "input"))
      (node (ref "R6") (pin "1") (pinfunction "1_1") (pintype "input"))
      (node (ref "RESET1") (pin "1") (pinfunction "1_1") (pintype "input"))
      (node (ref "RESET1") (pin "2") (pinfunction "2_2") (pintype "input"))
      (node (ref "SCREW1") (pin "1") (pinfunction "1_1") (pintype "input"))
      (node (ref "SCREW2") (pin "1") (pinfunction "1_1") (pintype "input"))
      (node (ref "SCREW3") (pin "1") (pinfunction "1_1") (pintype "input"))
      (node (ref "SCREW4") (pin "1") (pinfunction "1_1") (pintype "input"))
      (node (ref "U1") (pin "19") (pinfunction "TESTEN_19") (pintype "unspecified"))
      (node (ref "U1") (pin "57") (pinfunction "GND_57") (pintype "bidirectional"))
      (node (ref "U2") (pin "4") (pinfunction "GND_4") (pintype "unspecified"))
      (node (ref "U3") (pin "2") (pinfunction "GND_2") (pintype "input"))
      (node (ref "U3") (pin "4") (pinfunction "GND_4") (pintype "input"))
      (node (ref "U4") (pin "3") (pinfunction "VSS_3") (pintype "unspecified"))
      (node (ref "U4") (pin "5") (pinfunction "SDO_5") (pintype "unspecified"))
      (node (ref "U4") (pin "8") (pinfunction "VSS_8") (pintype "unspecified"))
      (node (ref "U4") (pin "9") (pinfunction "VSS_9") (pintype "unspecified"))
      (node (ref "U5") (pin "10") (pinfunction "GND_10") (pintype "unspecified"))
      (node (ref "U5") (pin "12") (pinfunction "GND_12") (pintype "unspecified"))
      (node (ref "U5") (pin "13") (pinfunction "GND_13") (pintype "unspecified"))
      (node (ref "U5") (pin "24") (pinfunction "GND_24") (pintype "unspecified"))
      (node (ref "U6") (pin "18") (pinfunction "GND_18") (pintype "unspecified"))
      (node (ref "U6") (pin "25") (pinfunction "EP_25") (pintype "unspecified"))
      (node (ref "U6") (pin "9") (pinfunction "SDO/AD0_9") (pintype "unspecified"))
      (node (ref "USB4") (pin "A1B12") (pinfunction "GND_A1B12") (pintype "unspecified"))
      (node (ref "USB4") (pin "B1A12") (pinfunction "GND_B1A12") (pintype "unspecified"))
    )
    (net (code "13") (name "GPIO25") (class "Default")
      (node (ref "R4") (pin "2") (pinfunction "2_2") (pintype "input"))
      (node (ref "U1") (pin "37") (pinfunction "GPIO25_37") (pintype "bidirectional"))
    )
    (net (code "14") (name "GPSRX") (class "Default")
      (node (ref "U1") (pin "2") (pinfunction "GPIO0_2") (pintype "bidirectional"))
      (node (ref "U5") (pin "21") (pinfunction "GPS_RXD_21") (pintype "unspecified"))
    )
    (net (code "15") (name "GPSTX") (class "Default")
      (node (ref "U1") (pin "3") (pinfunction "GPIO1_3") (pintype "bidirectional"))
      (node (ref "U5") (pin "20") (pinfunction "GPS_TXD_20") (pintype "unspecified"))
    )
    (net (code "16") (name "IO2") (class "Default")
      (node (ref "H3") (pin "1") (pinfunction "1_1") (pintype "unspecified"))
      (node (ref "U1") (pin "4") (pinfunction "GPIO2_4") (pintype "bidirectional"))
    )
    (net (code "17") (name "IO3") (class "Default")
      (node (ref "H3") (pin "2") (pinfunction "2_2") (pintype "unspecified"))
      (node (ref "U1") (pin "5") (pinfunction "GPIO3_5") (pintype "bidirectional"))
    )
    (net (code "18") (name "IO18") (class "Default")
      (node (ref "H3") (pin "3") (pinfunction "3_3") (pintype "unspecified"))
      (node (ref "U1") (pin "29") (pinfunction "GPIO18_29") (pintype "bidirectional"))
    )
    (net (code "19") (name "IO19") (class "Default")
      (node (ref "H3") (pin "4") (pinfunction "4_4") (pintype "unspecified"))
      (node (ref "U1") (pin "30") (pinfunction "GPIO19_30") (pintype "bidirectional"))
    )
    (net (code "20") (name "IO20") (class "Default")
      (node (ref "H3") (pin "5") (pinfunction "5_5") (pintype "unspecified"))
      (node (ref "U1") (pin "31") (pinfunction "GPIO20_31") (pintype "bidirectional"))
    )
    (net (code "21") (name "IO26") (class "Default")
      (node (ref "H3") (pin "6") (pinfunction "6_6") (pintype "unspecified"))
      (node (ref "U1") (pin "38") (pinfunction "GPIO26_ADC0_38") (pintype "bidirectional"))
    )
    (net (code "22") (name "Net-(BOOTSEL1-Pad3)") (class "Default")
      (node (ref "BOOTSEL1") (pin "3") (pinfunction "3_3") (pintype "input"))
      (node (ref "BOOTSEL1") (pin "4") (pinfunction "4_4") (pintype "input"))
      (node (ref "R13") (pin "2") (pinfunction "2_2") (pintype "input"))
    )
    (net (code "23") (name "Net-(C10-Pad2)") (class "Default")
      (node (ref "C10") (pin "2") (pinfunction "2_2") (pintype "input"))
      (node (ref "R10") (pin "2") (pinfunction "2_2") (pintype "input"))
      (node (ref "U3") (pin "3") (pinfunction "3_3") (pintype "input"))
    )
    (net (code "24") (name "Net-(LED1-A)") (class "Default")
      (node (ref "LED1") (pin "2") (pinfunction "A_2") (pintype "input"))
      (node (ref "R3") (pin "2") (pinfunction "2_2") (pintype "input"))
    )
    (net (code "25") (name "Net-(LED2-A)") (class "Default")
      (node (ref "LED2") (pin "2") (pinfunction "A_2") (pintype "input"))
      (node (ref "R4") (pin "1") (pinfunction "1_1") (pintype "input"))
    )
    (net (code "26") (name "Net-(Q1-D)") (class "Default")
      (node (ref "C7") (pin "2") (pinfunction "2_2") (pintype "unspecified"))
      (node (ref "Q1") (pin "3") (pinfunction "D_3") (pintype "unspecified"))
      (node (ref "R5") (pin "2") (pinfunction "2_2") (pintype "input"))
      (node (ref "R6") (pin "2") (pinfunction "2_2") (pintype "input"))
    )
    (net (code "27") (name "Net-(U1-USB_DM)") (class "Default")
      (node (ref "R15") (pin "1") (pinfunction "1_1") (pintype "input"))
      (node (ref "U1") (pin "46") (pinfunction "USB_DM_46") (pintype "bidirectional"))
    )
    (net (code "28") (name "Net-(U1-USB_DP)") (class "Default")
      (node (ref "R14") (pin "1") (pinfunction "1_1") (pintype "input"))
      (node (ref "U1") (pin "47") (pinfunction "USB_DP_47") (pintype "bidirectional"))
    )
    (net (code "29") (name "Net-(U5-VCC_RF)") (class "Default")
      (node (ref "L1") (pin "1") (pinfunction "1_1") (pintype "input"))
      (node (ref "U5") (pin "9") (pinfunction "VCC_RF_9") (pintype "unspecified"))
    )
    (net (code "30") (name "Net-(U6-REGOUT)") (class "Default")
      (node (ref "C26") (pin "1") (pinfunction "1_1") (pintype "input"))
      (node (ref "U6") (pin "10") (pinfunction "REGOUT_10") (pintype "unspecified"))
    )
    (net (code "31") (name "Net-(USB4-CC1)") (class "Default")
      (node (ref "R19") (pin "2") (pinfunction "2_2") (pintype "input"))
      (node (ref "USB4") (pin "A5") (pinfunction "CC1_A5") (pintype "unspecified"))
    )
    (net (code "32") (name "Net-(USB4-CC2)") (class "Default")
      (node (ref "R18") (pin "2") (pinfunction "2_2") (pintype "input"))
      (node (ref "USB4") (pin "B5") (pinfunction "CC2_B5") (pintype "unspecified"))
    )
    (net (code "33") (name "QSPI_SCLK") (class "Default")
      (node (ref "U1") (pin "52") (pinfunction "QSPI_SCLK_52") (pintype "output"))
      (node (ref "U2") (pin "6") (pinfunction "CLK_6") (pintype "unspecified"))
    )
    (net (code "34") (name "QSPI_SD0") (class "Default")
      (node (ref "U1") (pin "53") (pinfunction "QSPI_SD0_53") (pintype "bidirectional"))
      (node (ref "U2") (pin "5") (pinfunction "DI_5") (pintype "unspecified"))
    )
    (net (code "35") (name "QSPI_SD1") (class "Default")
      (node (ref "U1") (pin "55") (pinfunction "QSPI_SD1_55") (pintype "bidirectional"))
      (node (ref "U2") (pin "2") (pinfunction "DO_2") (pintype "unspecified"))
    )
    (net (code "36") (name "QSPI_SD2") (class "Default")
      (node (ref "U1") (pin "54") (pinfunction "QSPI_SD2_54") (pintype "bidirectional"))
      (node (ref "U2") (pin "3") (pinfunction "IO2_3") (pintype "unspecified"))
    )
    (net (code "37") (name "QSPI_SD3") (class "Default")
      (node (ref "U1") (pin "51") (pinfunction "QSPI_SD3_51") (pintype "bidirectional"))
      (node (ref "U2") (pin "7") (pinfunction "IO3_7") (pintype "unspecified"))
    )
    (net (code "38") (name "QSPI_SS") (class "Default")
      (node (ref "R12") (pin "2") (pinfunction "2_2") (pintype "input"))
      (node (ref "R13") (pin "1") (pinfunction "1_1") (pintype "input"))
      (node (ref "U1") (pin "56") (pinfunction "QSPI_SS_56") (pintype "bidirectional"))
      (node (ref "U2") (pin "1") (pinfunction "CS#_1") (pintype "unspecified"))
    )
    (net (code "39") (name "SCL") (class "Default")
      (node (ref "R20") (pin "1") (pinfunction "1_1") (pintype "input"))
      (node (ref "R22") (pin "1") (pinfunction "1_1") (pintype "input"))
      (node (ref "U1") (pin "7") (pinfunction "GPIO5_7") (pintype "bidirectional"))
      (node (ref "U4") (pin "2") (pinfunction "SCK_2") (pintype "unspecified"))
      (node (ref "U6") (pin "23") (pinfunction "SCL/SCLK_23") (pintype "unspecified"))
    )
    (net (code "40") (name "SDA") (class "Default")
      (node (ref "R21") (pin "1") (pinfunction "1_1") (pintype "input"))
      (node (ref "R23") (pin "1") (pinfunction "1_1") (pintype "input"))
      (node (ref "U1") (pin "6") (pinfunction "GPIO4_6") (pintype "bidirectional"))
      (node (ref "U4") (pin "4") (pinfunction "SDI_4") (pintype "unspecified"))
      (node (ref "U6") (pin "24") (pinfunction "SDA/SDI_24") (pintype "unspecified"))
    )
    (net (code "41") (name "USBD+") (class "Default")
      (node (ref "R14") (pin "2") (pinfunction "2_2") (pintype "input"))
      (node (ref "USB4") (pin "A6") (pinfunction "Dp1_A6") (pintype "unspecified"))
      (node (ref "USB4") (pin "B6") (pinfunction "Dp2_B6") (pintype "unspecified"))
    )
    (net (code "42") (name "USBD-") (class "Default")
      (node (ref "R15") (pin "2") (pinfunction "2_2") (pintype "input"))
      (node (ref "USB4") (pin "A7") (pinfunction "Dn1_A7") (pintype "unspecified"))
      (node (ref "USB4") (pin "B7") (pinfunction "Dn2_B7") (pintype "unspecified"))
    )
    (net (code "43") (name "VBUS") (class "Default")
      (node (ref "USB4") (pin "A4B9") (pinfunction "VBUS_A4B9") (pintype "unspecified"))
      (node (ref "USB4") (pin "B4A9") (pinfunction "VBUS_B4A9") (pintype "unspecified"))
    )
    (net (code "44") (name "VSYS") (class "Default")
      (node (ref "C1") (pin "2") (pinfunction "2_2") (pintype "input"))
      (node (ref "C2") (pin "2") (pinfunction "2_2") (pintype "unspecified"))
      (node (ref "H9") (pin "1") (pinfunction "1_1") (pintype "unspecified"))
      (node (ref "LDO1") (pin "1") (pinfunction "VIN_1") (pintype "unspecified"))
      (node (ref "LDO1") (pin "3") (pinfunction "CE_3") (pintype "unspecified"))
      (node (ref "R5") (pin "1") (pinfunction "1_1") (pintype "input"))
    )
    (net (code "45") (name "unconnected-(LDO1-NC-Pad4)") (class "Default")
      (node (ref "LDO1") (pin "4") (pinfunction "NC_4") (pintype "unspecified+no_connect"))
    )
    (net (code "46") (name "unconnected-(U1-GPIO6-Pad8)") (class "Default")
      (node (ref "U1") (pin "8") (pinfunction "GPIO6_8") (pintype "bidirectional+no_connect"))
    )
    (net (code "47") (name "unconnected-(U1-GPIO7-Pad9)") (class "Default")
      (node (ref "U1") (pin "9") (pinfunction "GPIO7_9") (pintype "bidirectional+no_connect"))
    )
    (net (code "48") (name "unconnected-(U1-GPIO8-Pad11)") (class "Default")
      (node (ref "U1") (pin "11") (pinfunction "GPIO8_11") (pintype "bidirectional+no_connect"))
    )
    (net (code "49") (name "unconnected-(U1-GPIO9-Pad12)") (class "Default")
      (node (ref "U1") (pin "12") (pinfunction "GPIO9_12") (pintype "bidirectional+no_connect"))
    )
    (net (code "50") (name "unconnected-(U1-GPIO10-Pad13)") (class "Default")
      (node (ref "U1") (pin "13") (pinfunction "GPIO10_13") (pintype "bidirectional+no_connect"))
    )
    (net (code "51") (name "unconnected-(U1-GPIO11-Pad14)") (class "Default")
      (node (ref "U1") (pin "14") (pinfunction "GPIO11_14") (pintype "bidirectional+no_connect"))
    )
    (net (code "52") (name "unconnected-(U1-GPIO12-Pad15)") (class "Default")
      (node (ref "U1") (pin "15") (pinfunction "GPIO12_15") (pintype "bidirectional+no_connect"))
    )
    (net (code "53") (name "unconnected-(U1-GPIO13-Pad16)") (class "Default")
      (node (ref "U1") (pin "16") (pinfunction "GPIO13_16") (pintype "bidirectional+no_connect"))
    )
    (net (code "54") (name "unconnected-(U1-GPIO14-Pad17)") (class "Default")
      (node (ref "U1") (pin "17") (pinfunction "GPIO14_17") (pintype "bidirectional+no_connect"))
    )
    (net (code "55") (name "unconnected-(U1-GPIO15-Pad18)") (class "Default")
      (node (ref "U1") (pin "18") (pinfunction "GPIO15_18") (pintype "bidirectional+no_connect"))
    )
    (net (code "56") (name "unconnected-(U1-GPIO16-Pad27)") (class "Default")
      (node (ref "U1") (pin "27") (pinfunction "GPIO16_27") (pintype "bidirectional+no_connect"))
    )
    (net (code "57") (name "unconnected-(U1-GPIO17-Pad28)") (class "Default")
      (node (ref "U1") (pin "28") (pinfunction "GPIO17_28") (pintype "bidirectional+no_connect"))
    )
    (net (code "58") (name "unconnected-(U1-GPIO21-Pad32)") (class "Default")
      (node (ref "U1") (pin "32") (pinfunction "GPIO21_32") (pintype "bidirectional+no_connect"))
    )
    (net (code "59") (name "unconnected-(U1-GPIO22-Pad34)") (class "Default")
      (node (ref "U1") (pin "34") (pinfunction "GPIO22_34") (pintype "bidirectional+no_connect"))
    )
    (net (code "60") (name "unconnected-(U1-GPIO23-Pad35)") (class "Default")
      (node (ref "U1") (pin "35") (pinfunction "GPIO23_35") (pintype "bidirectional+no_connect"))
    )
    (net (code "61") (name "unconnected-(U1-GPIO24-Pad36)") (class "Default")
      (node (ref "U1") (pin "36") (pinfunction "GPIO24_36") (pintype "bidirectional+no_connect"))
    )
    (net (code "62") (name "unconnected-(U1-GPIO27_ADC1-Pad39)") (class "Default")
      (node (ref "U1") (pin "39") (pinfunction "GPIO27_ADC1_39") (pintype "bidirectional+no_connect"))
    )
    (net (code "63") (name "unconnected-(U1-GPIO28_ADC2-Pad40)") (class "Default")
      (node (ref "U1") (pin "40") (pinfunction "GPIO28_ADC2_40") (pintype "bidirectional+no_connect"))
    )
    (net (code "64") (name "unconnected-(U4-INT-Pad7)") (class "Default")
      (node (ref "U4") (pin "7") (pinfunction "INT_7") (pintype "unspecified+no_connect"))
    )
    (net (code "65") (name "unconnected-(U5-NC-Pad1)") (class "Default")
      (node (ref "U5") (pin "1") (pinfunction "NC_1") (pintype "unspecified+no_connect"))
    )
    (net (code "66") (name "unconnected-(U5-NC-Pad2)") (class "Default")
      (node (ref "U5") (pin "2") (pinfunction "NC_2") (pintype "unspecified+no_connect"))
    )
    (net (code "67") (name "unconnected-(U5-NC-Pad4)") (class "Default")
      (node (ref "U5") (pin "4") (pinfunction "NC_4") (pintype "unspecified+no_connect"))
    )
    (net (code "68") (name "unconnected-(U5-NC-Pad5)") (class "Default")
      (node (ref "U5") (pin "5") (pinfunction "NC_5") (pintype "unspecified+no_connect"))
    )
    (net (code "69") (name "unconnected-(U5-NC-Pad6)") (class "Default")
      (node (ref "U5") (pin "6") (pinfunction "NC_6") (pintype "unspecified+no_connect"))
    )
    (net (code "70") (name "unconnected-(U5-NC-Pad7)") (class "Default")
      (node (ref "U5") (pin "7") (pinfunction "NC_7") (pintype "unspecified+no_connect"))
    )
    (net (code "71") (name "unconnected-(U5-NC-Pad14)") (class "Default")
      (node (ref "U5") (pin "14") (pinfunction "NC_14") (pintype "unspecified+no_connect"))
    )
    (net (code "72") (name "unconnected-(U5-NC-Pad15)") (class "Default")
      (node (ref "U5") (pin "15") (pinfunction "NC_15") (pintype "unspecified+no_connect"))
    )
    (net (code "73") (name "unconnected-(U5-NC-Pad18)") (class "Default")
      (node (ref "U5") (pin "18") (pinfunction "NC_18") (pintype "unspecified+no_connect"))
    )
    (net (code "74") (name "unconnected-(U5-NC-Pad19)") (class "Default")
      (node (ref "U5") (pin "19") (pinfunction "NC_19") (pintype "unspecified+no_connect"))
    )
    (net (code "75") (name "unconnected-(U5-PPS-Pad3)") (class "Default")
      (node (ref "U5") (pin "3") (pinfunction "PPS_3") (pintype "unspecified+no_connect"))
    )
    (net (code "76") (name "unconnected-(U5-RESET-Pad8)") (class "Default")
      (node (ref "U5") (pin "8") (pinfunction "RESET_8") (pintype "unspecified+no_connect"))
    )
    (net (code "77") (name "unconnected-(U5-RF_IN-Pad11)") (class "Default")
      (node (ref "U5") (pin "11") (pinfunction "RF_IN_11") (pintype "unspecified+no_connect"))
    )
    (net (code "78") (name "unconnected-(U5-RX2-Pad17)") (class "Default")
      (node (ref "U5") (pin "17") (pinfunction "RX2_17") (pintype "unspecified+no_connect"))
    )
    (net (code "79") (name "unconnected-(U5-TX2-Pad16)") (class "Default")
      (node (ref "U5") (pin "16") (pinfunction "TX2_16") (pintype "unspecified+no_connect"))
    )
    (net (code "80") (name "unconnected-(U6-AUX_CL-Pad7)") (class "Default")
      (node (ref "U6") (pin "7") (pinfunction "AUX_CL_7") (pintype "unspecified+no_connect"))
    )
    (net (code "81") (name "unconnected-(U6-AUX_DA-Pad21)") (class "Default")
      (node (ref "U6") (pin "21") (pinfunction "AUX_DA_21") (pintype "unspecified+no_connect"))
    )
    (net (code "82") (name "unconnected-(U6-FSYNC-Pad11)") (class "Default")
      (node (ref "U6") (pin "11") (pinfunction "FSYNC_11") (pintype "unspecified+no_connect"))
    )
    (net (code "83") (name "unconnected-(U6-INT1-Pad12)") (class "Default")
      (node (ref "U6") (pin "12") (pinfunction "INT1_12") (pintype "unspecified+no_connect"))
    )
    (net (code "84") (name "unconnected-(U6-NC-Pad1)") (class "Default")
      (node (ref "U6") (pin "1") (pinfunction "NC_1") (pintype "unspecified+no_connect"))
    )
    (net (code "85") (name "unconnected-(U6-NC-Pad2)") (class "Default")
      (node (ref "U6") (pin "2") (pinfunction "NC_2") (pintype "unspecified+no_connect"))
    )
    (net (code "86") (name "unconnected-(U6-NC-Pad3)") (class "Default")
      (node (ref "U6") (pin "3") (pinfunction "NC_3") (pintype "unspecified+no_connect"))
    )
    (net (code "87") (name "unconnected-(U6-NC-Pad4)") (class "Default")
      (node (ref "U6") (pin "4") (pinfunction "NC_4") (pintype "unspecified+no_connect"))
    )
    (net (code "88") (name "unconnected-(U6-NC-Pad5)") (class "Default")
      (node (ref "U6") (pin "5") (pinfunction "NC_5") (pintype "unspecified+no_connect"))
    )
    (net (code "89") (name "unconnected-(U6-NC-Pad6)") (class "Default")
      (node (ref "U6") (pin "6") (pinfunction "NC_6") (pintype "unspecified+no_connect"))
    )
    (net (code "90") (name "unconnected-(U6-NC-Pad14)") (class "Default")
      (node (ref "U6") (pin "14") (pinfunction "NC_14") (pintype "unspecified+no_connect"))
    )
    (net (code "91") (name "unconnected-(U6-NC-Pad15)") (class "Default")
      (node (ref "U6") (pin "15") (pinfunction "NC_15") (pintype "unspecified+no_connect"))
    )
    (net (code "92") (name "unconnected-(U6-NC-Pad16)") (class "Default")
      (node (ref "U6") (pin "16") (pinfunction "NC_16") (pintype "unspecified+no_connect"))
    )
    (net (code "93") (name "unconnected-(U6-NC-Pad17)") (class "Default")
      (node (ref "U6") (pin "17") (pinfunction "NC_17") (pintype "unspecified+no_connect"))
    )
    (net (code "94") (name "unconnected-(U6-RESV-Pad19)") (class "Default")
      (node (ref "U6") (pin "19") (pinfunction "RESV_19") (pintype "unspecified+no_connect"))
    )
    (net (code "95") (name "unconnected-(U6-RESV-Pad20)") (class "Default")
      (node (ref "U6") (pin "20") (pinfunction "RESV_20") (pintype "unspecified+no_connect"))
    )
    (net (code "96") (name "unconnected-(USB4-EH-Pad13)") (class "Default")
      (node (ref "USB4") (pin "13") (pinfunction "EH_13") (pintype "unspecified+no_connect"))
    )
    (net (code "97") (name "unconnected-(USB4-EH-Pad14)") (class "Default")
      (node (ref "USB4") (pin "14") (pinfunction "EH_14") (pintype "unspecified+no_connect"))
    )
    (net (code "98") (name "unconnected-(USB4-SBU1-PadA8)") (class "Default")
      (node (ref "USB4") (pin "A8") (pinfunction "SBU1_A8") (pintype "unspecified+no_connect"))
    )
    (net (code "99") (name "unconnected-(USB4-SBU2-PadB8)") (class "Default")
      (node (ref "USB4") (pin "B8") (pinfunction "SBU2_B8") (pintype "unspecified+no_connect"))
    )
  )
)
